# RWR.net
KiCad netlist of a schematic drawn in Altium Designer
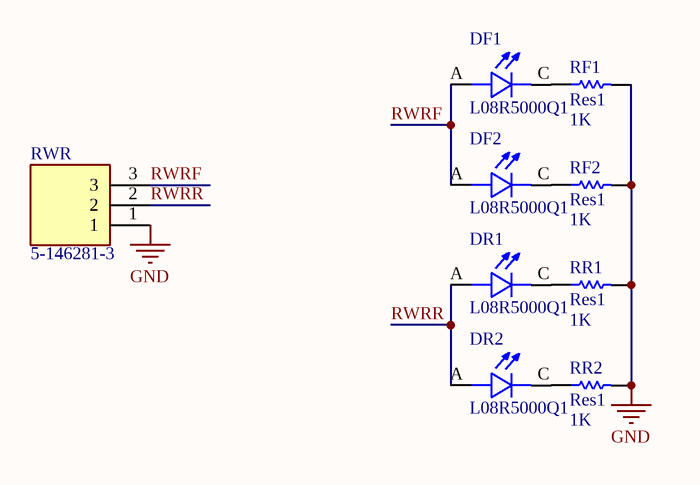
[diagram p0: RWR.SchDoc]

(export (version "E")
  (design (tool "Eeschema 10.0.6"))
  (components
    (comp (ref "DF1")
      (value "L08R5000Q1")
      (footprint "LEDRD254W57D500H1070")
      (description "LED, Orange, Through Hole, T-1 3/4 (5mm), 30 mA, 2.1 V, 635 nm")
      (libsource (lib "L08R5000Q1") (part "L08R5000Q1"))
    )
    (comp (ref "DF2")
      (value "L08R5000Q1")
      (footprint "LEDRD254W57D500H1070")
      (description "LED, Orange, Through Hole, T-1 3/4 (5mm), 30 mA, 2.1 V, 635 nm")
      (libsource (lib "L08R5000Q1") (part "L08R5000Q1"))
    )
    (comp (ref "DR1")
      (value "L08R5000Q1")
      (footprint "LEDRD254W57D500H1070")
      (description "LED, Orange, Through Hole, T-1 3/4 (5mm), 30 mA, 2.1 V, 635 nm")
      (libsource (lib "L08R5000Q1") (part "L08R5000Q1"))
    )
    (comp (ref "DR2")
      (value "L08R5000Q1")
      (footprint "LEDRD254W57D500H1070")
      (description "LED, Orange, Through Hole, T-1 3/4 (5mm), 30 mA, 2.1 V, 635 nm")
      (libsource (lib "L08R5000Q1") (part "L08R5000Q1"))
    )
    (comp (ref "RF1")
      (value "Res1")
      (footprint "AXIAL-0.3")
      (description "Resistor")
      (fields (field (name "ALTIUM_VALUE") "1K") (field (name "PUBLISHER") "Altium Limited"))
      (libsource (lib "Miscellaneous Devices") (part "Res1"))
    )
    (comp (ref "RF2")
      (value "Res1")
      (footprint "AXIAL-0.3")
      (description "Resistor")
      (fields (field (name "ALTIUM_VALUE") "1K") (field (name "PUBLISHER") "Altium Limited"))
      (libsource (lib "Miscellaneous Devices") (part "Res1"))
    )
    (comp (ref "RR1")
      (value "Res1")
      (footprint "AXIAL-0.3")
      (description "Resistor")
      (fields (field (name "ALTIUM_VALUE") "1K") (field (name "PUBLISHER") "Altium Limited"))
      (libsource (lib "Miscellaneous Devices") (part "Res1"))
    )
    (comp (ref "RR2")
      (value "Res1")
      (footprint "AXIAL-0.3")
      (description "Resistor")
      (fields (field (name "ALTIUM_VALUE") "1K") (field (name "PUBLISHER") "Altium Limited"))
      (libsource (lib "Miscellaneous Devices") (part "Res1"))
    )
    (comp (ref "RWR")
      (value "5-146281-3")
      (footprint "TE_5-146281-3")
      (description "Header; Conn; Interconnect System; PCB Plug; 3 Cont; Thru-Hole; Breakaway; Straight; 3A")
      (fields (field (name "MF") "TE Connectivity"))
      (libsource (lib "5-146281-3") (part "5-146281-3"))
    )
  )
  (nets
    (net (code "1") (name "/RWRF") (class "Default")
      (node (ref "DF1") (pin "A") (pinfunction "A_A") (pintype "passive"))
      (node (ref "DF2") (pin "A") (pinfunction "A_A") (pintype "passive"))
      (node (ref "RWR") (pin "3") (pinfunction "3_3") (pintype "passive"))
    )
    (net (code "2") (name "/RWRR") (class "Default")
      (node (ref "DR1") (pin "A") (pinfunction "A_A") (pintype "passive"))
      (node (ref "DR2") (pin "A") (pinfunction "A_A") (pintype "passive"))
      (node (ref "RWR") (pin "2") (pinfunction "2_2") (pintype "passive"))
    )
    (net (code "3") (name "GND") (class "Default")
      (node (ref "RF1") (pin "2") (pinfunction "2_2") (pintype "passive"))
      (node (ref "RF2") (pin "2") (pinfunction "2_2") (pintype "passive"))
      (node (ref "RR1") (pin "2") (pinfunction "2_2") (pintype "passive"))
      (node (ref "RR2") (pin "2") (pinfunction "2_2") (pintype "passive"))
      (node (ref "RWR") (pin "1") (pinfunction "1_1") (pintype "passive"))
    )
    (net (code "4") (name "Net-(DF1-PadC)") (class "Default")
      (node (ref "DF1") (pin "C") (pinfunction "C_C") (pintype "passive"))
      (node (ref "RF1") (pin "1") (pinfunction "1_1") (pintype "passive"))
    )
    (net (code "5") (name "Net-(DF2-PadC)") (class "Default")
      (node (ref "DF2") (pin "C") (pinfunction "C_C") (pintype "passive"))
      (node (ref "RF2") (pin "1") (pinfunction "1_1") (pintype "passive"))
    )
    (net (code "6") (name "Net-(DR1-PadC)") (class "Default")
      (node (ref "DR1") (pin "C") (pinfunction "C_C") (pintype "passive"))
      (node (ref "RR1") (pin "1") (pinfunction "1_1") (pintype "passive"))
    )
    (net (code "7") (name "Net-(DR2-PadC)") (class "Default")
      (node (ref "DR2") (pin "C") (pinfunction "C_C") (pintype "passive"))
      (node (ref "RR2") (pin "1") (pinfunction "1_1") (pintype "passive"))
    )
  )
)
